# design.net
KiCad netlist of a schematic drawn in Altium Designer
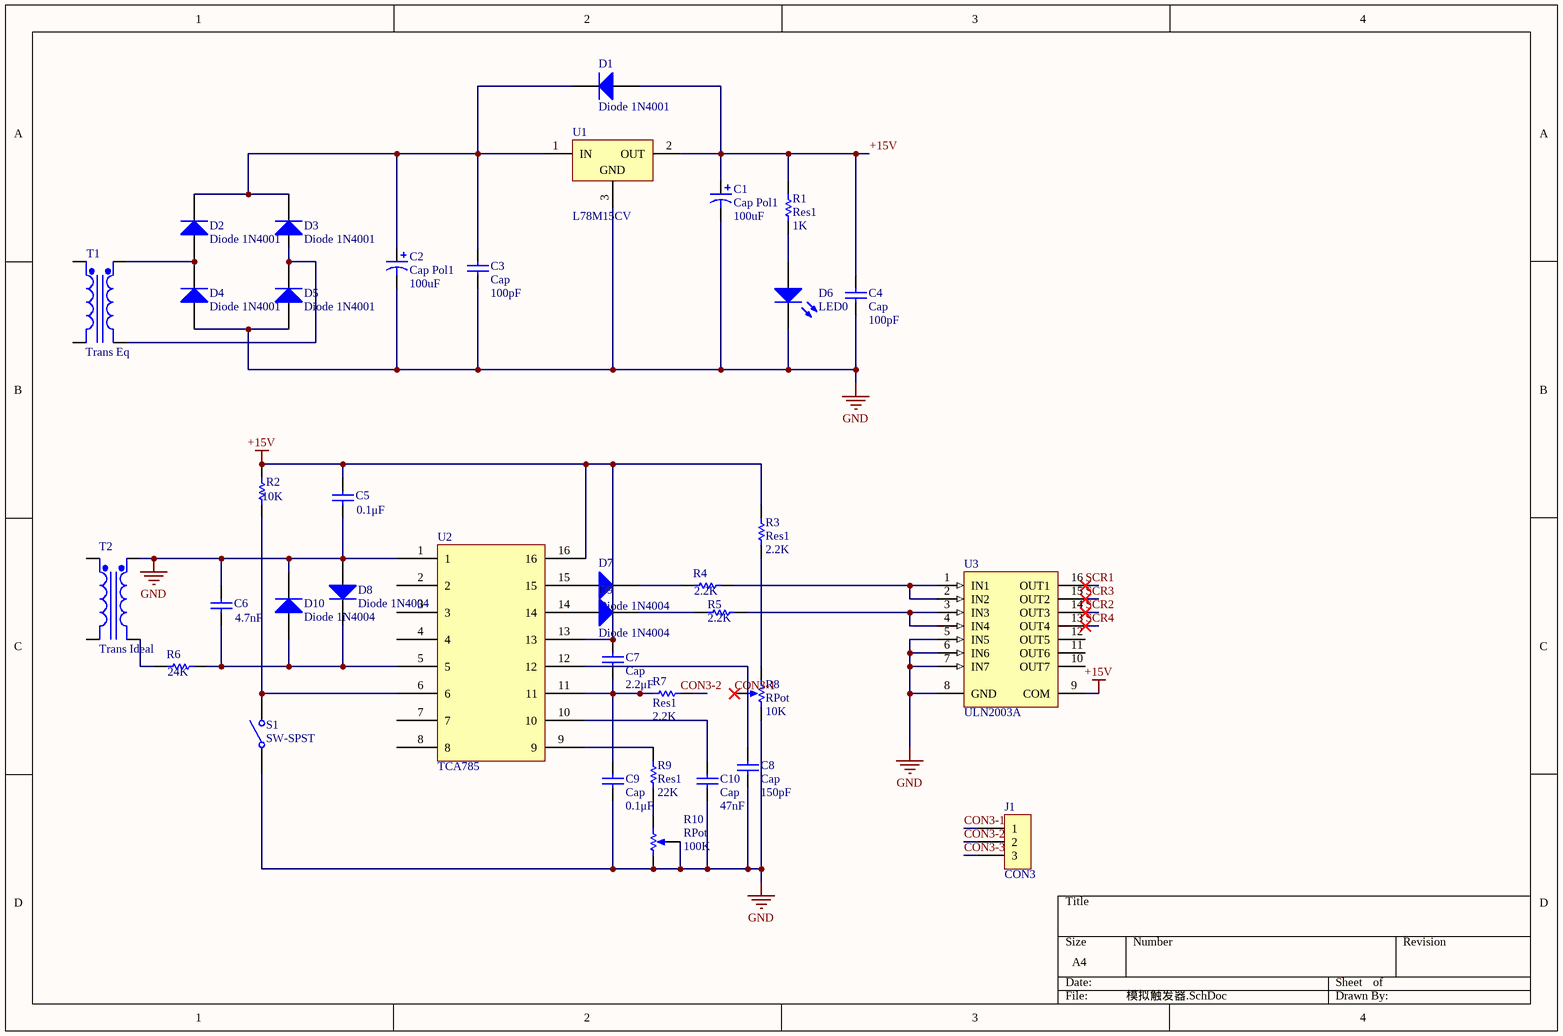
[diagram p0: 模拟触发器.SchDoc]

(export (version "E")
  (design (tool "Eeschema 10.0.6"))
  (components
    (comp (ref "C1")
      (value "Cap Pol1")
      (footprint "RB7.6-15")
      (description "Polarized Capacitor (Radial)")
      (fields (field (name "ALTIUM_VALUE") "100uF") (field (name "PUBLISHER") "Altium Limited"))
      (libsource (lib "Miscellaneous Devices") (part "Cap Pol1"))
    )
    (comp (ref "C2")
      (value "Cap Pol1")
      (footprint "RB7.6-15")
      (description "Polarized Capacitor (Radial)")
      (fields (field (name "ALTIUM_VALUE") "100uF") (field (name "PUBLISHER") "Altium Limited"))
      (libsource (lib "Miscellaneous Devices") (part "Cap Pol1"))
    )
    (comp (ref "C3")
      (value "Cap")
      (footprint "6-0805")
      (description "Capacitor")
      (fields (field (name "ALTIUM_VALUE") "100pF") (field (name "PUBLISHER") "Altium Limited"))
      (libsource (lib "Miscellaneous Devices") (part "Cap"))
    )
    (comp (ref "C4")
      (value "Cap")
      (footprint "6-0805")
      (description "Capacitor")
      (fields (field (name "ALTIUM_VALUE") "100pF") (field (name "PUBLISHER") "Altium Limited"))
      (libsource (lib "Miscellaneous Devices") (part "Cap"))
    )
    (comp (ref "C5")
      (value "0.1μF")
      (footprint "6-0805")
      (description "Capacitor")
      (fields (field (name "Comment") "Cap") (field (name "PUBLISHER") "Altium Limited"))
      (libsource (lib "Miscellaneous Devices") (part "Cap"))
    )
    (comp (ref "C6")
      (value "4.7nF")
      (footprint "6-0805")
      (description "Capacitor")
      (fields (field (name "Comment") "Cap") (field (name "PUBLISHER") "Altium Limited"))
      (libsource (lib "Miscellaneous Devices") (part "Cap"))
    )
    (comp (ref "C7")
      (value "Cap")
      (footprint "6-0805")
      (description "Capacitor")
      (fields (field (name "ALTIUM_VALUE") "2.2μF") (field (name "PUBLISHER") "Altium Limited"))
      (libsource (lib "Miscellaneous Devices") (part "Cap"))
    )
    (comp (ref "C8")
      (value "Cap")
      (footprint "6-0805")
      (description "Capacitor")
      (fields (field (name "ALTIUM_VALUE") "150pF") (field (name "PUBLISHER") "Altium Limited"))
      (libsource (lib "Miscellaneous Devices") (part "Cap"))
    )
    (comp (ref "C9")
      (value "Cap")
      (footprint "6-0805")
      (description "Capacitor")
      (fields (field (name "ALTIUM_VALUE") "0.1μF") (field (name "PUBLISHER") "Altium Limited"))
      (libsource (lib "Miscellaneous Devices") (part "Cap"))
    )
    (comp (ref "C10")
      (value "Cap")
      (footprint "6-0805")
      (description "Capacitor")
      (fields (field (name "ALTIUM_VALUE") "47nF") (field (name "PUBLISHER") "Altium Limited"))
      (libsource (lib "Miscellaneous Devices") (part "Cap"))
    )
    (comp (ref "D1")
      (value "Diode 1N4001")
      (footprint "DO-41")
      (description "1 Amp General Purpose Rectifier")
      (fields (field (name "PUBLISHER") "Altium Limited"))
      (libsource (lib "Miscellaneous Devices") (part "Diode 1N4001"))
    )
    (comp (ref "D2")
      (value "Diode 1N4001")
      (footprint "DO-41")
      (description "1 Amp General Purpose Rectifier")
      (fields (field (name "PUBLISHER") "Altium Limited"))
      (libsource (lib "Miscellaneous Devices") (part "Diode 1N4001"))
    )
    (comp (ref "D3")
      (value "Diode 1N4001")
      (footprint "DO-41")
      (description "1 Amp General Purpose Rectifier")
      (fields (field (name "PUBLISHER") "Altium Limited"))
      (libsource (lib "Miscellaneous Devices") (part "Diode 1N4001"))
    )
    (comp (ref "D4")
      (value "Diode 1N4001")
      (footprint "DO-41")
      (description "1 Amp General Purpose Rectifier")
      (fields (field (name "PUBLISHER") "Altium Limited"))
      (libsource (lib "Miscellaneous Devices") (part "Diode 1N4001"))
    )
    (comp (ref "D5")
      (value "Diode 1N4001")
      (footprint "DO-41")
      (description "1 Amp General Purpose Rectifier")
      (fields (field (name "PUBLISHER") "Altium Limited"))
      (libsource (lib "Miscellaneous Devices") (part "Diode 1N4001"))
    )
    (comp (ref "D6")
      (value "LED0")
      (footprint "6-0805")
      (description "Typical INFRARED GaAs LED")
      (fields (field (name "PUBLISHER") "Altium Limited"))
      (libsource (lib "Miscellaneous Devices") (part "LED0"))
    )
    (comp (ref "D7")
      (value "Diode 1N4004")
      (footprint "DO-41")
      (description "1 Amp General Purpose Rectifier")
      (fields (field (name "PUBLISHER") "Altium Limited"))
      (libsource (lib "Miscellaneous Devices") (part "Diode 1N4004"))
    )
    (comp (ref "D8")
      (value "Diode 1N4004")
      (footprint "DO-41")
      (description "1 Amp General Purpose Rectifier")
      (fields (field (name "PUBLISHER") "Altium Limited"))
      (libsource (lib "Miscellaneous Devices") (part "Diode 1N4004"))
    )
    (comp (ref "D9")
      (value "Diode 1N4004")
      (footprint "DO-41")
      (description "1 Amp General Purpose Rectifier")
      (fields (field (name "PUBLISHER") "Altium Limited"))
      (libsource (lib "Miscellaneous Devices") (part "Diode 1N4004"))
    )
    (comp (ref "D10")
      (value "Diode 1N4004")
      (footprint "DO-41")
      (description "1 Amp General Purpose Rectifier")
      (fields (field (name "PUBLISHER") "Altium Limited"))
      (libsource (lib "Miscellaneous Devices") (part "Diode 1N4004"))
    )
    (comp (ref "J1") (value "CON3") (footprint "DG1283-5.0") (libsource (lib "常用元件库") (part "CON3")))
    (comp (ref "R1")
      (value "Res1")
      (footprint "6-0805")
      (description "Resistor")
      (fields (field (name "ALTIUM_VALUE") "1K") (field (name "PUBLISHER") "Altium Limited"))
      (libsource (lib "Miscellaneous Devices") (part "Res1"))
    )
    (comp (ref "R2")
      (value "10K")
      (footprint "6-0805")
      (description "Resistor")
      (fields (field (name "Comment") "Res1") (field (name "PUBLISHER") "Altium Limited"))
      (libsource (lib "Miscellaneous Devices") (part "Res1"))
    )
    (comp (ref "R3")
      (value "Res1")
      (footprint "6-0805")
      (description "Resistor")
      (fields (field (name "ALTIUM_VALUE") "2.2K") (field (name "PUBLISHER") "Altium Limited"))
      (libsource (lib "Miscellaneous Devices") (part "Res1"))
    )
    (comp (ref "R4")
      (value "2.2K")
      (footprint "6-0805")
      (description "Resistor")
      (fields (field (name "Comment") "Res1") (field (name "PUBLISHER") "Altium Limited"))
      (libsource (lib "Miscellaneous Devices") (part "Res1"))
    )
    (comp (ref "R5")
      (value "2.2K")
      (footprint "6-0805")
      (description "Resistor")
      (fields (field (name "Comment") "Res1") (field (name "PUBLISHER") "Altium Limited"))
      (libsource (lib "Miscellaneous Devices") (part "Res1"))
    )
    (comp (ref "R6")
      (value "24K")
      (footprint "1206")
      (description "Resistor")
      (fields (field (name "Comment") "Res1") (field (name "PUBLISHER") "Altium Limited"))
      (libsource (lib "Miscellaneous Devices") (part "Res1"))
    )
    (comp (ref "R7")
      (value "Res1")
      (footprint "6-0805")
      (description "Resistor")
      (fields (field (name "ALTIUM_VALUE") "2.2K") (field (name "PUBLISHER") "Altium Limited"))
      (libsource (lib "Miscellaneous Devices") (part "Res1"))
    )
    (comp (ref "R8")
      (value "RPot")
      (footprint "VR5")
      (description "Potentiometer")
      (fields (field (name "ALTIUM_VALUE") "10K") (field (name "PUBLISHER") "Altium Limited"))
      (libsource (lib "Miscellaneous Devices") (part "RPot"))
    )
    (comp (ref "R9")
      (value "Res1")
      (footprint "6-0805")
      (description "Resistor")
      (fields (field (name "ALTIUM_VALUE") "22K") (field (name "PUBLISHER") "Altium Limited"))
      (libsource (lib "Miscellaneous Devices") (part "Res1"))
    )
    (comp (ref "R10")
      (value "RPot")
      (footprint "VR5")
      (description "Potentiometer")
      (fields (field (name "ALTIUM_VALUE") "100K") (field (name "PUBLISHER") "Altium Limited"))
      (libsource (lib "Miscellaneous Devices") (part "RPot"))
    )
    (comp (ref "S1")
      (value "SW-SPST")
      (footprint "SPST-2")
      (description "Single-Pole, Single-Throw Switch")
      (fields (field (name "PUBLISHER") "Altium Limited"))
      (libsource (lib "Miscellaneous Devices") (part "SW-SPST"))
    )
    (comp (ref "T1")
      (value "Trans Eq")
      (footprint "TRF_4")
      (description "Transformer (Equivalent Circuit Model)")
      (fields (field (name "PUBLISHER") "Altium Limited"))
      (libsource (lib "Miscellaneous Devices") (part "Trans Eq"))
    )
    (comp (ref "T2")
      (value "Trans Ideal")
      (footprint "TRF_4")
      (description "Transformer (Ideal)")
      (fields (field (name "PUBLISHER") "Altium Limited"))
      (libsource (lib "Miscellaneous Devices") (part "Trans Ideal"))
    )
    (comp (ref "U1")
      (value "L78M15CV")
      (footprint "TO220V")
      (description "Positive Voltage Regulator")
      (fields (field (name "PUBLISHER") "Altium Limited"))
      (libsource (lib "ST Power Mgt Voltage Regulator") (part "L78M15CV"))
    )
    (comp (ref "U2")
      (value "TCA785")
      (footprint "Miscellaneous Devices:DIP-16")
      (libsource (lib "TCA785") (part "TCA785"))
    )
    (comp (ref "U3")
      (value "ULN2003A")
      (footprint "A16")
      (description "High-Voltage, High-Current Darlington Array")
      (fields (field (name "PUBLISHER") "Altium Limited"))
      (libsource (lib "Allegro Interface Darlington Driver") (part "ULN2003A"))
    )
  )
  (nets
    (net (code "1") (name "+15V") (class "Default")
      (node (ref "C1") (pin "1") (pinfunction "1_1") (pintype "passive"))
      (node (ref "C4") (pin "2") (pinfunction "2_2") (pintype "passive"))
      (node (ref "C5") (pin "2") (pinfunction "2_2") (pintype "passive"))
      (node (ref "C7") (pin "2") (pinfunction "2_2") (pintype "passive"))
      (node (ref "D1") (pin "1") (pinfunction "A_1") (pintype "passive"))
      (node (ref "R1") (pin "2") (pinfunction "2_2") (pintype "passive"))
      (node (ref "R2") (pin "2") (pinfunction "2_2") (pintype "passive"))
      (node (ref "R3") (pin "2") (pinfunction "2_2") (pintype "passive"))
      (node (ref "U1") (pin "2") (pinfunction "OUT_2") (pintype "power_in"))
      (node (ref "U2") (pin "13") (pinfunction "13_13") (pintype "passive"))
      (node (ref "U2") (pin "16") (pinfunction "16_16") (pintype "passive"))
      (node (ref "U3") (pin "9") (pinfunction "COM_9") (pintype "passive"))
    )
    (net (code "2") (name "/CON3-1") (class "Default")
      (node (ref "J1") (pin "1") (pinfunction "1_1") (pintype "passive"))
      (node (ref "R8") (pin "3") (pinfunction "TAP_3") (pintype "passive"))
    )
    (net (code "3") (name "/CON3-2") (class "Default")
      (node (ref "J1") (pin "2") (pinfunction "2_2") (pintype "passive"))
    )
    (net (code "4") (name "/CON3-3") (class "Default")
      (node (ref "J1") (pin "3") (pinfunction "3_3") (pintype "passive"))
    )
    (net (code "5") (name "/SCR1") (class "Default")
      (node (ref "U3") (pin "16") (pinfunction "OUT1_16") (pintype "open_collector+no_connect"))
    )
    (net (code "6") (name "/SCR2") (class "Default")
      (node (ref "U3") (pin "14") (pinfunction "OUT3_14") (pintype "open_collector+no_connect"))
    )
    (net (code "7") (name "/SCR3") (class "Default")
      (node (ref "U3") (pin "15") (pinfunction "OUT2_15") (pintype "open_collector+no_connect"))
    )
    (net (code "8") (name "/SCR4") (class "Default")
      (node (ref "U3") (pin "13") (pinfunction "OUT4_13") (pintype "open_collector+no_connect"))
    )
    (net (code "9") (name "GND") (class "Default")
      (node (ref "C1") (pin "2") (pinfunction "2_2") (pintype "passive"))
      (node (ref "C10") (pin "1") (pinfunction "1_1") (pintype "passive"))
      (node (ref "C2") (pin "2") (pinfunction "2_2") (pintype "passive"))
      (node (ref "C3") (pin "1") (pinfunction "1_1") (pintype "passive"))
      (node (ref "C4") (pin "1") (pinfunction "1_1") (pintype "passive"))
      (node (ref "C5") (pin "1") (pinfunction "1_1") (pintype "passive"))
      (node (ref "C6") (pin "2") (pinfunction "2_2") (pintype "passive"))
      (node (ref "C8") (pin "1") (pinfunction "1_1") (pintype "passive"))
      (node (ref "C9") (pin "1") (pinfunction "1_1") (pintype "passive"))
      (node (ref "D10") (pin "2") (pinfunction "K_2") (pintype "passive"))
      (node (ref "D4") (pin "1") (pinfunction "A_1") (pintype "passive"))
      (node (ref "D5") (pin "1") (pinfunction "A_1") (pintype "passive"))
      (node (ref "D6") (pin "2") (pinfunction "K_2") (pintype "passive"))
      (node (ref "D8") (pin "1") (pinfunction "A_1") (pintype "passive"))
      (node (ref "R10") (pin "1") (pinfunction "TOP_1") (pintype "passive"))
      (node (ref "R10") (pin "3") (pinfunction "TAP_3") (pintype "passive"))
      (node (ref "R8") (pin "2") (pinfunction "BOT_2") (pintype "passive"))
      (node (ref "S1") (pin "1") (pinfunction "COMMON_1") (pintype "passive"))
      (node (ref "T2") (pin "3") (pinfunction "Sec+_3") (pintype "passive"))
      (node (ref "U1") (pin "3") (pinfunction "GND_3") (pintype "power_in"))
      (node (ref "U2") (pin "1") (pinfunction "1_1") (pintype "passive"))
      (node (ref "U3") (pin "5") (pinfunction "IN5_5") (pintype "input"))
      (node (ref "U3") (pin "6") (pinfunction "IN6_6") (pintype "input"))
      (node (ref "U3") (pin "7") (pinfunction "IN7_7") (pintype "input"))
      (node (ref "U3") (pin "8") (pinfunction "GND_8") (pintype "power_in"))
    )
    (net (code "10") (name "Net-(C7-Pad1)") (class "Default")
      (node (ref "C7") (pin "1") (pinfunction "1_1") (pintype "passive"))
      (node (ref "C9") (pin "2") (pinfunction "2_2") (pintype "passive"))
      (node (ref "R7") (pin "2") (pinfunction "2_2") (pintype "passive"))
      (node (ref "U2") (pin "11") (pinfunction "11_11") (pintype "passive"))
    )
    (net (code "11") (name "Net-(C8-Pad2)") (class "Default")
      (node (ref "C8") (pin "2") (pinfunction "2_2") (pintype "passive"))
      (node (ref "U2") (pin "12") (pinfunction "12_12") (pintype "passive"))
    )
    (net (code "12") (name "Net-(C10-Pad2)") (class "Default")
      (node (ref "C10") (pin "2") (pinfunction "2_2") (pintype "passive"))
      (node (ref "U2") (pin "10") (pinfunction "10_10") (pintype "passive"))
    )
    (net (code "13") (name "Net-(D1-K)") (class "Default")
      (node (ref "C2") (pin "1") (pinfunction "1_1") (pintype "passive"))
      (node (ref "C3") (pin "2") (pinfunction "2_2") (pintype "passive"))
      (node (ref "D1") (pin "2") (pinfunction "K_2") (pintype "passive"))
      (node (ref "D2") (pin "2") (pinfunction "K_2") (pintype "passive"))
      (node (ref "D3") (pin "2") (pinfunction "K_2") (pintype "passive"))
      (node (ref "U1") (pin "1") (pinfunction "IN_1") (pintype "power_in"))
    )
    (net (code "14") (name "Net-(D2-A)") (class "Default")
      (node (ref "D2") (pin "1") (pinfunction "A_1") (pintype "passive"))
      (node (ref "D4") (pin "2") (pinfunction "K_2") (pintype "passive"))
      (node (ref "T1") (pin "3") (pinfunction "Sec+_3") (pintype "passive"))
    )
    (net (code "15") (name "Net-(D3-A)") (class "Default")
      (node (ref "D3") (pin "1") (pinfunction "A_1") (pintype "passive"))
      (node (ref "D5") (pin "2") (pinfunction "K_2") (pintype "passive"))
      (node (ref "T1") (pin "4") (pinfunction "Sec-_4") (pintype "passive"))
    )
    (net (code "16") (name "Net-(D6-A)") (class "Default")
      (node (ref "D6") (pin "1") (pinfunction "A_1") (pintype "passive"))
      (node (ref "R1") (pin "1") (pinfunction "1_1") (pintype "passive"))
    )
    (net (code "17") (name "Net-(D7-K)") (class "Default")
      (node (ref "D7") (pin "2") (pinfunction "K_2") (pintype "passive"))
      (node (ref "R4") (pin "2") (pinfunction "2_2") (pintype "passive"))
    )
    (net (code "18") (name "Net-(D9-K)") (class "Default")
      (node (ref "D9") (pin "2") (pinfunction "K_2") (pintype "passive"))
      (node (ref "R5") (pin "2") (pinfunction "2_2") (pintype "passive"))
    )
    (net (code "19") (name "Net-(D10-A)") (class "Default")
      (node (ref "C6") (pin "1") (pinfunction "1_1") (pintype "passive"))
      (node (ref "D10") (pin "1") (pinfunction "A_1") (pintype "passive"))
      (node (ref "D8") (pin "2") (pinfunction "K_2") (pintype "passive"))
      (node (ref "R6") (pin "1") (pinfunction "1_1") (pintype "passive"))
      (node (ref "U2") (pin "5") (pinfunction "5_5") (pintype "passive"))
    )
    (net (code "20") (name "Net-(R8-TOP)") (class "Default")
      (node (ref "R3") (pin "1") (pinfunction "1_1") (pintype "passive"))
      (node (ref "R8") (pin "1") (pinfunction "TOP_1") (pintype "passive"))
    )
    (net (code "21") (name "Net-(R9-Pad2)") (class "Default")
      (node (ref "R9") (pin "2") (pinfunction "2_2") (pintype "passive"))
      (node (ref "U2") (pin "9") (pinfunction "9_9") (pintype "passive"))
    )
    (net (code "22") (name "Net-(R10-BOT)") (class "Default")
      (node (ref "R10") (pin "2") (pinfunction "BOT_2") (pintype "passive"))
      (node (ref "R9") (pin "1") (pinfunction "1_1") (pintype "passive"))
    )
    (net (code "23") (name "Net-(S1-NO)") (class "Default")
      (node (ref "R2") (pin "1") (pinfunction "1_1") (pintype "passive"))
      (node (ref "S1") (pin "2") (pinfunction "NO_2") (pintype "passive"))
      (node (ref "U2") (pin "6") (pinfunction "6_6") (pintype "passive"))
    )
    (net (code "24") (name "Net-(T2-Sec-)") (class "Default")
      (node (ref "R6") (pin "2") (pinfunction "2_2") (pintype "passive"))
      (node (ref "T2") (pin "4") (pinfunction "Sec-_4") (pintype "passive"))
    )
    (net (code "25") (name "Net-(U3-IN1)") (class "Default")
      (node (ref "R4") (pin "1") (pinfunction "1_1") (pintype "passive"))
      (node (ref "U3") (pin "1") (pinfunction "IN1_1") (pintype "input"))
      (node (ref "U3") (pin "2") (pinfunction "IN2_2") (pintype "input"))
    )
    (net (code "26") (name "Net-(U3-IN3)") (class "Default")
      (node (ref "R5") (pin "1") (pinfunction "1_1") (pintype "passive"))
      (node (ref "U3") (pin "3") (pinfunction "IN3_3") (pintype "input"))
      (node (ref "U3") (pin "4") (pinfunction "IN4_4") (pintype "input"))
    )
    (net (code "27") (name "unconnected-(D7-A-Pad1)") (class "Default")
      (node (ref "D7") (pin "1") (pinfunction "A_1") (pintype "passive"))
    )
    (net (code "28") (name "unconnected-(D9-A-Pad1)") (class "Default")
      (node (ref "D9") (pin "1") (pinfunction "A_1") (pintype "passive"))
    )
    (net (code "29") (name "unconnected-(R7-Pad1)") (class "Default")
      (node (ref "R7") (pin "1") (pinfunction "1_1") (pintype "passive"))
    )
    (net (code "30") (name "unconnected-(T1-Pri+-Pad1)") (class "Default")
      (node (ref "T1") (pin "1") (pinfunction "Pri+_1") (pintype "passive"))
    )
    (net (code "31") (name "unconnected-(T1-Pri--Pad2)") (class "Default")
      (node (ref "T1") (pin "2") (pinfunction "Pri-_2") (pintype "passive"))
    )
    (net (code "32") (name "unconnected-(T2-Pri+-Pad1)") (class "Default")
      (node (ref "T2") (pin "1") (pinfunction "Pri+_1") (pintype "passive"))
    )
    (net (code "33") (name "unconnected-(T2-Pri--Pad2)") (class "Default")
      (node (ref "T2") (pin "2") (pinfunction "Pri-_2") (pintype "passive"))
    )
    (net (code "34") (name "unconnected-(U2-Pad2)") (class "Default")
      (node (ref "U2") (pin "2") (pinfunction "2_2") (pintype "passive"))
    )
    (net (code "35") (name "unconnected-(U2-Pad3)") (class "Default")
      (node (ref "U2") (pin "3") (pinfunction "3_3") (pintype "passive"))
    )
    (net (code "36") (name "unconnected-(U2-Pad4)") (class "Default")
      (node (ref "U2") (pin "4") (pinfunction "4_4") (pintype "passive"))
    )
    (net (code "37") (name "unconnected-(U2-Pad7)") (class "Default")
      (node (ref "U2") (pin "7") (pinfunction "7_7") (pintype "passive"))
    )
    (net (code "38") (name "unconnected-(U2-Pad8)") (class "Default")
      (node (ref "U2") (pin "8") (pinfunction "8_8") (pintype "passive"))
    )
    (net (code "39") (name "unconnected-(U2-Pad14)") (class "Default")
      (node (ref "U2") (pin "14") (pinfunction "14_14") (pintype "passive"))
    )
    (net (code "40") (name "unconnected-(U2-Pad15)") (class "Default")
      (node (ref "U2") (pin "15") (pinfunction "15_15") (pintype "passive"))
    )
    (net (code "41") (name "unconnected-(U3-OUT5-Pad12)") (class "Default")
      (node (ref "U3") (pin "12") (pinfunction "OUT5_12") (pintype "open_collector"))
    )
    (net (code "42") (name "unconnected-(U3-OUT6-Pad11)") (class "Default")
      (node (ref "U3") (pin "11") (pinfunction "OUT6_11") (pintype "open_collector"))
    )
    (net (code "43") (name "unconnected-(U3-OUT7-Pad10)") (class "Default")
      (node (ref "U3") (pin "10") (pinfunction "OUT7_10") (pintype "open_collector"))
    )
  )
)
